# untitled.net
KiCad netlist of a schematic drawn in EAGLE
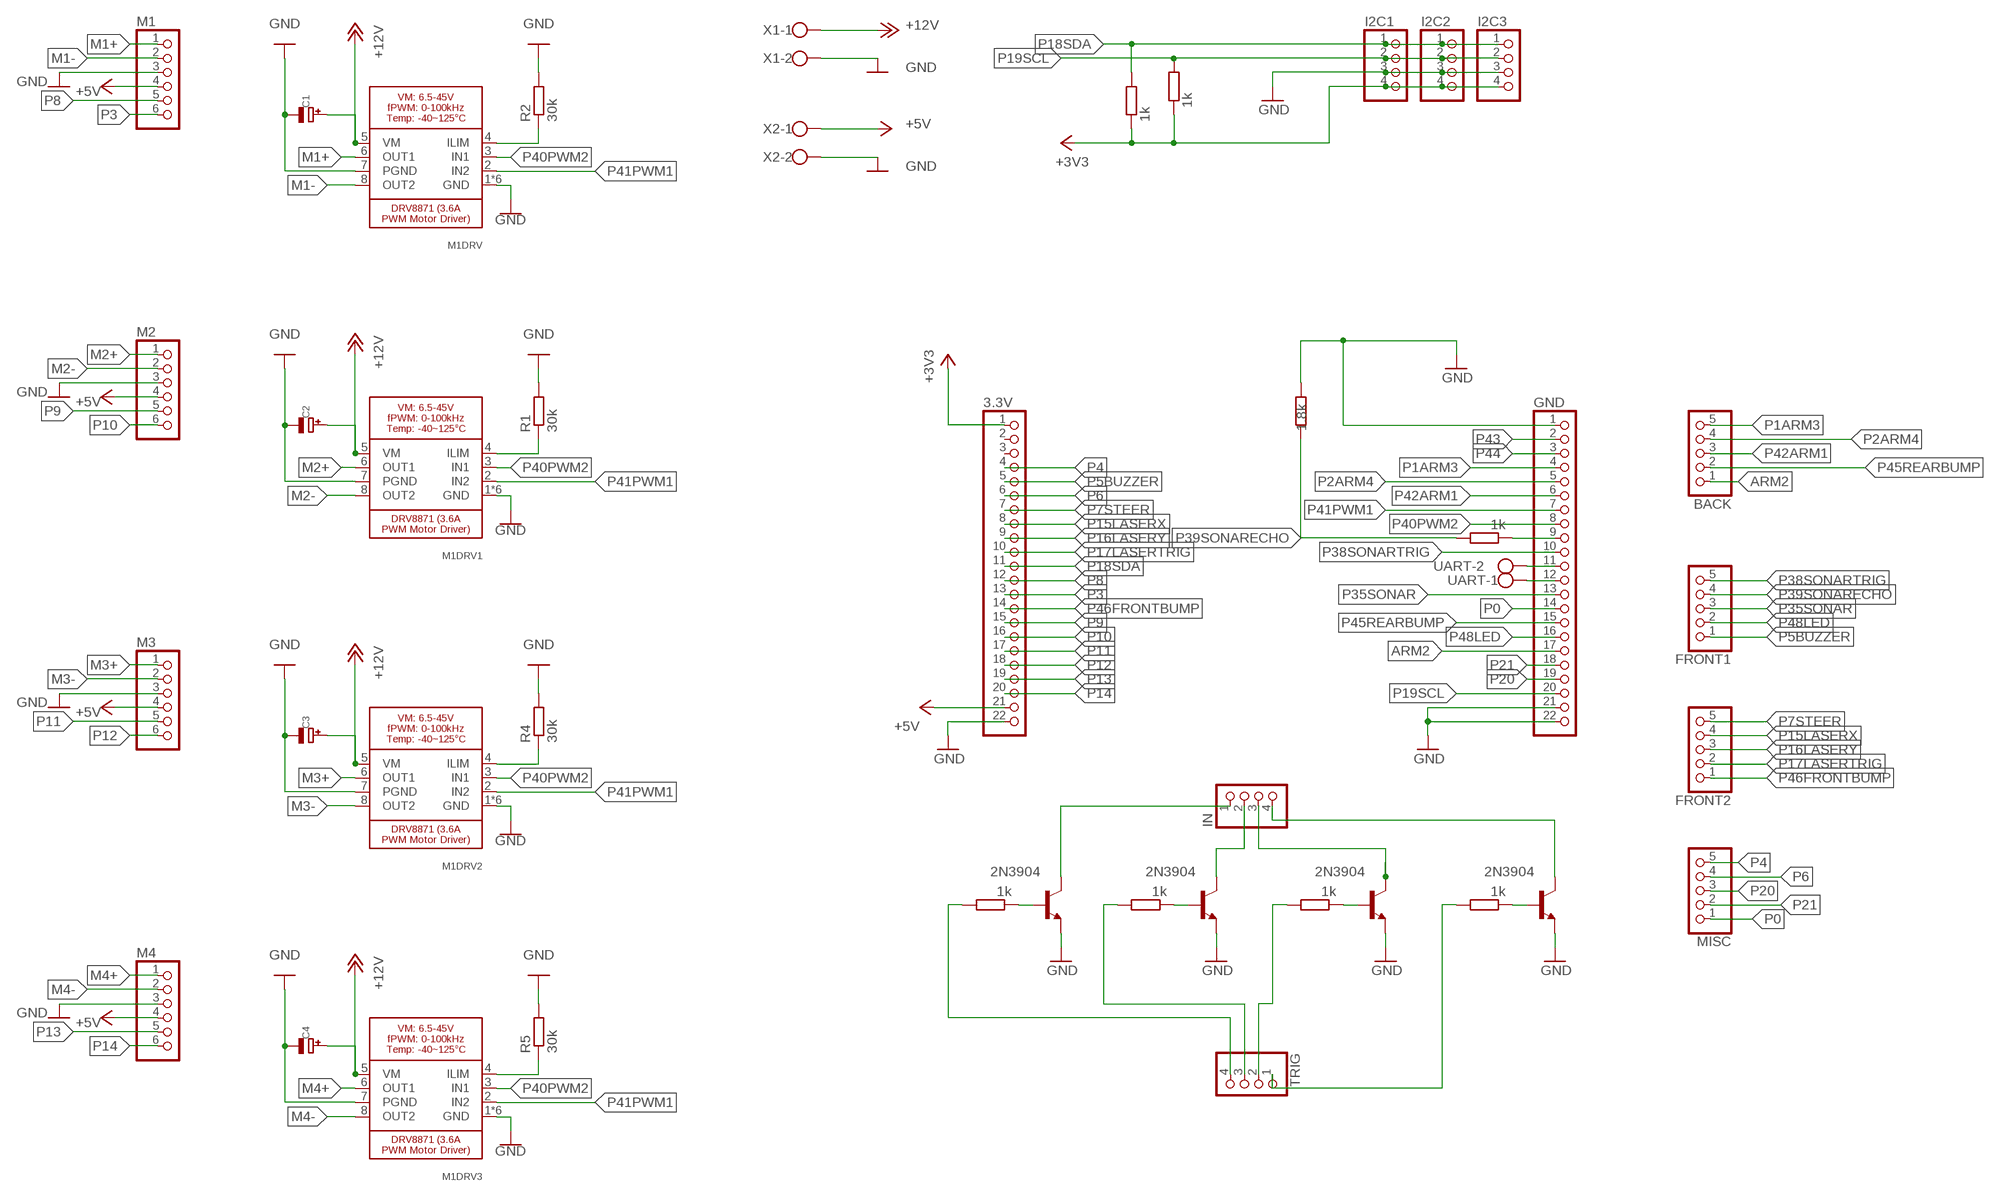
[diagram p0: schematic, sheet 1]

(export (version "E")
  (design (tool "Eeschema 10.0.6"))
  (components
    (comp (ref "1K")
      (value "1k")
      (footprint "eagle-import:0207_10")
      (libsource (lib "eagle-import") (part "R-EU_0207/10"))
    )
    (comp (ref "1K1")
      (value "1k")
      (footprint "eagle-import:0207_10")
      (libsource (lib "eagle-import") (part "R-EU_0207/10"))
    )
    (comp (ref "1K2")
      (value "1.8k")
      (footprint "eagle-import:0207_10")
      (libsource (lib "eagle-import") (part "R-EU_0207/10"))
    )
    (comp (ref "1K3")
      (value "1k")
      (footprint "eagle-import:0207_10")
      (libsource (lib "eagle-import") (part "R-EU_0207/10"))
    )
    (comp (ref "1K4")
      (value "1k")
      (footprint "eagle-import:0207_10")
      (libsource (lib "eagle-import") (part "R-EU_0207/10"))
    )
    (comp (ref "1K5")
      (value "1k")
      (footprint "eagle-import:0207_10")
      (libsource (lib "eagle-import") (part "R-EU_0207/10"))
    )
    (comp (ref "1K6")
      (value "1k")
      (footprint "eagle-import:0207_10")
      (libsource (lib "eagle-import") (part "R-EU_0207/10"))
    )
    (comp (ref "3.3V")
      (value "PINHD-1X22")
      (footprint "eagle-import:1X22")
      (libsource (lib "eagle-import") (part "PINHD-1X22"))
    )
    (comp (ref "BACK")
      (value "PINHD-1X5")
      (footprint "eagle-import:1X05")
      (libsource (lib "eagle-import") (part "PINHD-1X5"))
    )
    (comp (ref "C1")
      (value "MICROBUILDER_CAP_ELECTROLYTICPTH_3.5MMGRID_10MMDIA")
      (footprint "eagle-import:MICROBUILDER_CELEC_3.5MM_10MM")
      (libsource (lib "eagle-import") (part "MICROBUILDER_CAP_ELECTROLYTICPTH_3.5MMGRID_10MMDIA"))
    )
    (comp (ref "C2")
      (value "MICROBUILDER_CAP_ELECTROLYTICPTH_3.5MMGRID_10MMDIA")
      (footprint "eagle-import:MICROBUILDER_CELEC_3.5MM_10MM")
      (libsource (lib "eagle-import") (part "MICROBUILDER_CAP_ELECTROLYTICPTH_3.5MMGRID_10MMDIA"))
    )
    (comp (ref "C3")
      (value "MICROBUILDER_CAP_ELECTROLYTICPTH_3.5MMGRID_10MMDIA")
      (footprint "eagle-import:MICROBUILDER_CELEC_3.5MM_10MM")
      (libsource (lib "eagle-import") (part "MICROBUILDER_CAP_ELECTROLYTICPTH_3.5MMGRID_10MMDIA"))
    )
    (comp (ref "C4")
      (value "MICROBUILDER_CAP_ELECTROLYTICPTH_3.5MMGRID_10MMDIA")
      (footprint "eagle-import:MICROBUILDER_CELEC_3.5MM_10MM")
      (libsource (lib "eagle-import") (part "MICROBUILDER_CAP_ELECTROLYTICPTH_3.5MMGRID_10MMDIA"))
    )
    (comp (ref "FRONT1")
      (value "PINHD-1X5")
      (footprint "eagle-import:1X05")
      (libsource (lib "eagle-import") (part "PINHD-1X5"))
    )
    (comp (ref "FRONT2")
      (value "PINHD-1X5")
      (footprint "eagle-import:1X05")
      (libsource (lib "eagle-import") (part "PINHD-1X5"))
    )
    (comp (ref "GND")
      (value "PINHD-1X22")
      (footprint "eagle-import:1X22")
      (libsource (lib "eagle-import") (part "PINHD-1X22"))
    )
    (comp (ref "I2C1")
      (value "PINHD-1X4")
      (footprint "eagle-import:1X04")
      (libsource (lib "eagle-import") (part "PINHD-1X4"))
    )
    (comp (ref "I2C2")
      (value "PINHD-1X4")
      (footprint "eagle-import:1X04")
      (libsource (lib "eagle-import") (part "PINHD-1X4"))
    )
    (comp (ref "I2C3")
      (value "PINHD-1X4")
      (footprint "eagle-import:1X04")
      (libsource (lib "eagle-import") (part "PINHD-1X4"))
    )
    (comp (ref "IN")
      (value "PINHD-1X4")
      (footprint "eagle-import:1X04")
      (libsource (lib "eagle-import") (part "PINHD-1X4"))
    )
    (comp (ref "M1")
      (value "PINHD-1X6")
      (footprint "eagle-import:1X06")
      (libsource (lib "eagle-import") (part "PINHD-1X6"))
    )
    (comp (ref "M1DRV")
      (value "MICROBUILDER_DRV8871")
      (footprint "eagle-import:MICROBUILDER_HSOP8")
      (libsource (lib "eagle-import") (part "MICROBUILDER_DRV8871"))
    )
    (comp (ref "M1DRV1")
      (value "MICROBUILDER_DRV8871")
      (footprint "eagle-import:MICROBUILDER_HSOP8")
      (libsource (lib "eagle-import") (part "MICROBUILDER_DRV8871"))
    )
    (comp (ref "M1DRV2")
      (value "MICROBUILDER_DRV8871")
      (footprint "eagle-import:MICROBUILDER_HSOP8")
      (libsource (lib "eagle-import") (part "MICROBUILDER_DRV8871"))
    )
    (comp (ref "M1DRV3")
      (value "MICROBUILDER_DRV8871")
      (footprint "eagle-import:MICROBUILDER_HSOP8")
      (libsource (lib "eagle-import") (part "MICROBUILDER_DRV8871"))
    )
    (comp (ref "M2")
      (value "PINHD-1X6")
      (footprint "eagle-import:1X06")
      (libsource (lib "eagle-import") (part "PINHD-1X6"))
    )
    (comp (ref "M3")
      (value "PINHD-1X6")
      (footprint "eagle-import:1X06")
      (libsource (lib "eagle-import") (part "PINHD-1X6"))
    )
    (comp (ref "M4")
      (value "PINHD-1X6")
      (footprint "eagle-import:1X06")
      (libsource (lib "eagle-import") (part "PINHD-1X6"))
    )
    (comp (ref "MISC")
      (value "PINHD-1X5")
      (footprint "eagle-import:1X05")
      (libsource (lib "eagle-import") (part "PINHD-1X5"))
    )
    (comp (ref "R1")
      (value "30k")
      (footprint "eagle-import:0207_10")
      (libsource (lib "eagle-import") (part "R-EU_0207/10"))
    )
    (comp (ref "R2")
      (value "30k")
      (footprint "eagle-import:0207_10")
      (libsource (lib "eagle-import") (part "R-EU_0207/10"))
    )
    (comp (ref "R3")
      (value "1k")
      (footprint "eagle-import:0207_10")
      (libsource (lib "eagle-import") (part "R-EU_0207/10"))
    )
    (comp (ref "R4")
      (value "30k")
      (footprint "eagle-import:0207_10")
      (libsource (lib "eagle-import") (part "R-EU_0207/10"))
    )
    (comp (ref "R5")
      (value "30k")
      (footprint "eagle-import:0207_10")
      (libsource (lib "eagle-import") (part "R-EU_0207/10"))
    )
    (comp (ref "T1")
      (value "2N3904")
      (footprint "eagle-import:TO92")
      (libsource (lib "eagle-import") (part "2N3904"))
    )
    (comp (ref "T2")
      (value "2N3904")
      (footprint "eagle-import:TO92")
      (libsource (lib "eagle-import") (part "2N3904"))
    )
    (comp (ref "T3")
      (value "2N3904")
      (footprint "eagle-import:TO92")
      (libsource (lib "eagle-import") (part "2N3904"))
    )
    (comp (ref "T4")
      (value "2N3904")
      (footprint "eagle-import:TO92")
      (libsource (lib "eagle-import") (part "2N3904"))
    )
    (comp (ref "TRIG")
      (value "PINHD-1X4")
      (footprint "eagle-import:1X04")
      (libsource (lib "eagle-import") (part "PINHD-1X4"))
    )
    (comp (ref "UART")
      (value "W237-102")
      (footprint "eagle-import:W237-102")
      (fields (field (name "MPN") "237-102"))
      (libsource (lib "eagle-import") (part "W237-102"))
    )
    (comp (ref "X1")
      (value "W237-102")
      (footprint "eagle-import:W237-102")
      (fields (field (name "MPN") "237-102"))
      (libsource (lib "eagle-import") (part "W237-102"))
    )
    (comp (ref "X2")
      (value "W237-102")
      (footprint "eagle-import:W237-102")
      (fields (field (name "MPN") "237-102"))
      (libsource (lib "eagle-import") (part "W237-102"))
    )
  )
  (nets
    (net (code "1") (name "+3V3") (class "Default")
      (node (ref "1K") (pin "1") (pinfunction "1_1") (pintype "passive"))
      (node (ref "3.3V") (pin "1") (pinfunction "1_1") (pintype "passive"))
      (node (ref "I2C1") (pin "4") (pinfunction "4_4") (pintype "passive"))
      (node (ref "I2C2") (pin "4") (pinfunction "4_4") (pintype "passive"))
      (node (ref "I2C3") (pin "4") (pinfunction "4_4") (pintype "passive"))
      (node (ref "R3") (pin "1") (pinfunction "1_1") (pintype "passive"))
    )
    (net (code "2") (name "+5V") (class "Default")
      (node (ref "3.3V") (pin "21") (pinfunction "21_21") (pintype "passive"))
      (node (ref "M1") (pin "4") (pinfunction "4_4") (pintype "passive"))
      (node (ref "M2") (pin "4") (pinfunction "4_4") (pintype "passive"))
      (node (ref "M3") (pin "4") (pinfunction "4_4") (pintype "passive"))
      (node (ref "M4") (pin "4") (pinfunction "4_4") (pintype "passive"))
      (node (ref "X2") (pin "1") (pinfunction "KL_1") (pintype "passive"))
    )
    (net (code "3") (name "+12V") (class "Default")
      (node (ref "C1") (pin "+") (pinfunction "+_+") (pintype "passive"))
      (node (ref "C2") (pin "+") (pinfunction "+_+") (pintype "passive"))
      (node (ref "C3") (pin "+") (pinfunction "+_+") (pintype "passive"))
      (node (ref "C4") (pin "+") (pinfunction "+_+") (pintype "passive"))
      (node (ref "M1DRV") (pin "5") (pinfunction "VM_5") (pintype "power_in"))
      (node (ref "M1DRV1") (pin "5") (pinfunction "VM_5") (pintype "power_in"))
      (node (ref "M1DRV2") (pin "5") (pinfunction "VM_5") (pintype "power_in"))
      (node (ref "M1DRV3") (pin "5") (pinfunction "VM_5") (pintype "power_in"))
      (node (ref "X1") (pin "1") (pinfunction "KL_1") (pintype "passive"))
    )
    (net (code "4") (name "ARM2") (class "Default")
      (node (ref "BACK") (pin "1") (pinfunction "1_1") (pintype "passive"))
      (node (ref "GND") (pin "17") (pinfunction "17_17") (pintype "passive"))
    )
    (net (code "5") (name "GND") (class "Default")
      (node (ref "1K2") (pin "1") (pinfunction "1_1") (pintype "passive"))
      (node (ref "3.3V") (pin "22") (pinfunction "22_22") (pintype "passive"))
      (node (ref "C1") (pin "-") (pinfunction "-_-") (pintype "passive"))
      (node (ref "C2") (pin "-") (pinfunction "-_-") (pintype "passive"))
      (node (ref "C3") (pin "-") (pinfunction "-_-") (pintype "passive"))
      (node (ref "C4") (pin "-") (pinfunction "-_-") (pintype "passive"))
      (node (ref "GND") (pin "1") (pinfunction "1_1") (pintype "passive"))
      (node (ref "GND") (pin "21") (pinfunction "21_21") (pintype "passive"))
      (node (ref "GND") (pin "22") (pinfunction "22_22") (pintype "passive"))
      (node (ref "I2C1") (pin "3") (pinfunction "3_3") (pintype "passive"))
      (node (ref "I2C2") (pin "3") (pinfunction "3_3") (pintype "passive"))
      (node (ref "I2C3") (pin "3") (pinfunction "3_3") (pintype "passive"))
      (node (ref "M1") (pin "3") (pinfunction "3_3") (pintype "passive"))
      (node (ref "M1DRV") (pin "1") (pinfunction "GND_1") (pintype "power_in"))
      (node (ref "M1DRV") (pin "7") (pinfunction "PGND_7") (pintype "power_in"))
      (node (ref "M1DRV") (pin "GND") (pinfunction "GND_GND") (pintype "power_in"))
      (node (ref "M1DRV") (pin "P$1") (pinfunction "GND_P$1") (pintype "power_in"))
      (node (ref "M1DRV") (pin "P$2") (pinfunction "GND_P$2") (pintype "power_in"))
      (node (ref "M1DRV") (pin "P$3") (pinfunction "GND_P$3") (pintype "power_in"))
      (node (ref "M1DRV") (pin "P$4") (pinfunction "GND_P$4") (pintype "power_in"))
      (node (ref "M1DRV1") (pin "1") (pinfunction "GND_1") (pintype "power_in"))
      (node (ref "M1DRV1") (pin "7") (pinfunction "PGND_7") (pintype "power_in"))
      (node (ref "M1DRV1") (pin "GND") (pinfunction "GND_GND") (pintype "power_in"))
      (node (ref "M1DRV1") (pin "P$1") (pinfunction "GND_P$1") (pintype "power_in"))
      (node (ref "M1DRV1") (pin "P$2") (pinfunction "GND_P$2") (pintype "power_in"))
      (node (ref "M1DRV1") (pin "P$3") (pinfunction "GND_P$3") (pintype "power_in"))
      (node (ref "M1DRV1") (pin "P$4") (pinfunction "GND_P$4") (pintype "power_in"))
      (node (ref "M1DRV2") (pin "1") (pinfunction "GND_1") (pintype "power_in"))
      (node (ref "M1DRV2") (pin "7") (pinfunction "PGND_7") (pintype "power_in"))
      (node (ref "M1DRV2") (pin "GND") (pinfunction "GND_GND") (pintype "power_in"))
      (node (ref "M1DRV2") (pin "P$1") (pinfunction "GND_P$1") (pintype "power_in"))
      (node (ref "M1DRV2") (pin "P$2") (pinfunction "GND_P$2") (pintype "power_in"))
      (node (ref "M1DRV2") (pin "P$3") (pinfunction "GND_P$3") (pintype "power_in"))
      (node (ref "M1DRV2") (pin "P$4") (pinfunction "GND_P$4") (pintype "power_in"))
      (node (ref "M1DRV3") (pin "1") (pinfunction "GND_1") (pintype "power_in"))
      (node (ref "M1DRV3") (pin "7") (pinfunction "PGND_7") (pintype "power_in"))
      (node (ref "M1DRV3") (pin "GND") (pinfunction "GND_GND") (pintype "power_in"))
      (node (ref "M1DRV3") (pin "P$1") (pinfunction "GND_P$1") (pintype "power_in"))
      (node (ref "M1DRV3") (pin "P$2") (pinfunction "GND_P$2") (pintype "power_in"))
      (node (ref "M1DRV3") (pin "P$3") (pinfunction "GND_P$3") (pintype "power_in"))
      (node (ref "M1DRV3") (pin "P$4") (pinfunction "GND_P$4") (pintype "power_in"))
      (node (ref "M2") (pin "3") (pinfunction "3_3") (pintype "passive"))
      (node (ref "M3") (pin "3") (pinfunction "3_3") (pintype "passive"))
      (node (ref "M4") (pin "3") (pinfunction "3_3") (pintype "passive"))
      (node (ref "R1") (pin "2") (pinfunction "2_2") (pintype "passive"))
      (node (ref "R2") (pin "2") (pinfunction "2_2") (pintype "passive"))
      (node (ref "R4") (pin "2") (pinfunction "2_2") (pintype "passive"))
      (node (ref "R5") (pin "2") (pinfunction "2_2") (pintype "passive"))
      (node (ref "T1") (pin "3") (pinfunction "E_3") (pintype "passive"))
      (node (ref "T2") (pin "3") (pinfunction "E_3") (pintype "passive"))
      (node (ref "T3") (pin "3") (pinfunction "E_3") (pintype "passive"))
      (node (ref "T4") (pin "3") (pinfunction "E_3") (pintype "passive"))
      (node (ref "X1") (pin "2") (pinfunction "KL_2") (pintype "passive"))
      (node (ref "X2") (pin "2") (pinfunction "KL_2") (pintype "passive"))
    )
    (net (code "6") (name "M1+") (class "Default")
      (node (ref "M1") (pin "1") (pinfunction "1_1") (pintype "passive"))
      (node (ref "M1DRV") (pin "6") (pinfunction "OUT1_6") (pintype "output"))
    )
    (net (code "7") (name "M1-") (class "Default")
      (node (ref "M1") (pin "2") (pinfunction "2_2") (pintype "passive"))
      (node (ref "M1DRV") (pin "8") (pinfunction "OUT2_8") (pintype "output"))
    )
    (net (code "8") (name "M2+") (class "Default")
      (node (ref "M1DRV1") (pin "6") (pinfunction "OUT1_6") (pintype "output"))
      (node (ref "M2") (pin "1") (pinfunction "1_1") (pintype "passive"))
    )
    (net (code "9") (name "M2-") (class "Default")
      (node (ref "M1DRV1") (pin "8") (pinfunction "OUT2_8") (pintype "output"))
      (node (ref "M2") (pin "2") (pinfunction "2_2") (pintype "passive"))
    )
    (net (code "10") (name "M3+") (class "Default")
      (node (ref "M1DRV2") (pin "6") (pinfunction "OUT1_6") (pintype "output"))
      (node (ref "M3") (pin "1") (pinfunction "1_1") (pintype "passive"))
    )
    (net (code "11") (name "M3-") (class "Default")
      (node (ref "M1DRV2") (pin "8") (pinfunction "OUT2_8") (pintype "output"))
      (node (ref "M3") (pin "2") (pinfunction "2_2") (pintype "passive"))
    )
    (net (code "12") (name "M4+") (class "Default")
      (node (ref "M1DRV3") (pin "6") (pinfunction "OUT1_6") (pintype "output"))
      (node (ref "M4") (pin "1") (pinfunction "1_1") (pintype "passive"))
    )
    (net (code "13") (name "M4-") (class "Default")
      (node (ref "M1DRV3") (pin "8") (pinfunction "OUT2_8") (pintype "output"))
      (node (ref "M4") (pin "2") (pinfunction "2_2") (pintype "passive"))
    )
    (net (code "14") (name "Net-(1K1-Pad1)") (class "Default")
      (node (ref "1K1") (pin "1") (pinfunction "1_1") (pintype "passive"))
      (node (ref "GND") (pin "9") (pinfunction "9_9") (pintype "passive"))
    )
    (net (code "15") (name "Net-(1K3-Pad2)") (class "Default")
      (node (ref "1K3") (pin "2") (pinfunction "2_2") (pintype "passive"))
      (node (ref "TRIG") (pin "3") (pinfunction "3_3") (pintype "passive"))
    )
    (net (code "16") (name "Net-(1K4-Pad2)") (class "Default")
      (node (ref "1K4") (pin "2") (pinfunction "2_2") (pintype "passive"))
      (node (ref "TRIG") (pin "2") (pinfunction "2_2") (pintype "passive"))
    )
    (net (code "17") (name "Net-(1K5-Pad2)") (class "Default")
      (node (ref "1K5") (pin "2") (pinfunction "2_2") (pintype "passive"))
      (node (ref "TRIG") (pin "1") (pinfunction "1_1") (pintype "passive"))
    )
    (net (code "18") (name "Net-(1K6-Pad2)") (class "Default")
      (node (ref "1K6") (pin "2") (pinfunction "2_2") (pintype "passive"))
      (node (ref "TRIG") (pin "4") (pinfunction "4_4") (pintype "passive"))
    )
    (net (code "19") (name "Net-(M1DRV-ILIM)") (class "Default")
      (node (ref "M1DRV") (pin "4") (pinfunction "ILIM_4") (pintype "input"))
      (node (ref "R2") (pin "1") (pinfunction "1_1") (pintype "passive"))
    )
    (net (code "20") (name "Net-(M1DRV1-ILIM)") (class "Default")
      (node (ref "M1DRV1") (pin "4") (pinfunction "ILIM_4") (pintype "input"))
      (node (ref "R1") (pin "1") (pinfunction "1_1") (pintype "passive"))
    )
    (net (code "21") (name "Net-(M1DRV2-ILIM)") (class "Default")
      (node (ref "M1DRV2") (pin "4") (pinfunction "ILIM_4") (pintype "input"))
      (node (ref "R4") (pin "1") (pinfunction "1_1") (pintype "passive"))
    )
    (net (code "22") (name "Net-(M1DRV3-ILIM)") (class "Default")
      (node (ref "M1DRV3") (pin "4") (pinfunction "ILIM_4") (pintype "input"))
      (node (ref "R5") (pin "1") (pinfunction "1_1") (pintype "passive"))
    )
    (net (code "23") (name "Net-(T1-B)") (class "Default")
      (node (ref "1K3") (pin "1") (pinfunction "1_1") (pintype "passive"))
      (node (ref "T1") (pin "2") (pinfunction "B_2") (pintype "passive"))
    )
    (net (code "24") (name "Net-(T1-C)") (class "Default")
      (node (ref "IN") (pin "2") (pinfunction "2_2") (pintype "passive"))
      (node (ref "T1") (pin "1") (pinfunction "C_1") (pintype "passive"))
    )
    (net (code "25") (name "Net-(T2-B)") (class "Default")
      (node (ref "1K4") (pin "1") (pinfunction "1_1") (pintype "passive"))
      (node (ref "T2") (pin "2") (pinfunction "B_2") (pintype "passive"))
    )
    (net (code "26") (name "Net-(T2-C)") (class "Default")
      (node (ref "IN") (pin "3") (pinfunction "3_3") (pintype "passive"))
      (node (ref "T2") (pin "1") (pinfunction "C_1") (pintype "passive"))
    )
    (net (code "27") (name "Net-(T3-B)") (class "Default")
      (node (ref "1K5") (pin "1") (pinfunction "1_1") (pintype "passive"))
      (node (ref "T3") (pin "2") (pinfunction "B_2") (pintype "passive"))
    )
    (net (code "28") (name "Net-(T3-C)") (class "Default")
      (node (ref "IN") (pin "4") (pinfunction "4_4") (pintype "passive"))
      (node (ref "T3") (pin "1") (pinfunction "C_1") (pintype "passive"))
    )
    (net (code "29") (name "Net-(T4-B)") (class "Default")
      (node (ref "1K6") (pin "1") (pinfunction "1_1") (pintype "passive"))
      (node (ref "T4") (pin "2") (pinfunction "B_2") (pintype "passive"))
    )
    (net (code "30") (name "Net-(T4-C)") (class "Default")
      (node (ref "IN") (pin "1") (pinfunction "1_1") (pintype "passive"))
      (node (ref "T4") (pin "1") (pinfunction "C_1") (pintype "passive"))
    )
    (net (code "31") (name "Net-(UARTA-KL)") (class "Default")
      (node (ref "GND") (pin "12") (pinfunction "12_12") (pintype "passive"))
      (node (ref "UART") (pin "1") (pinfunction "KL_1") (pintype "passive"))
    )
    (net (code "32") (name "Net-(UARTB-KL)") (class "Default")
      (node (ref "GND") (pin "11") (pinfunction "11_11") (pintype "passive"))
      (node (ref "UART") (pin "2") (pinfunction "KL_2") (pintype "passive"))
    )
    (net (code "33") (name "P0") (class "Default")
      (node (ref "GND") (pin "14") (pinfunction "14_14") (pintype "passive"))
      (node (ref "MISC") (pin "1") (pinfunction "1_1") (pintype "passive"))
    )
    (net (code "34") (name "P1ARM3") (class "Default")
      (node (ref "BACK") (pin "5") (pinfunction "5_5") (pintype "passive"))
      (node (ref "GND") (pin "4") (pinfunction "4_4") (pintype "passive"))
    )
    (net (code "35") (name "P2ARM4") (class "Default")
      (node (ref "BACK") (pin "4") (pinfunction "4_4") (pintype "passive"))
      (node (ref "GND") (pin "5") (pinfunction "5_5") (pintype "passive"))
    )
    (net (code "36") (name "P3") (class "Default")
      (node (ref "3.3V") (pin "13") (pinfunction "13_13") (pintype "passive"))
      (node (ref "M1") (pin "6") (pinfunction "6_6") (pintype "passive"))
    )
    (net (code "37") (name "P4") (class "Default")
      (node (ref "3.3V") (pin "4") (pinfunction "4_4") (pintype "passive"))
      (node (ref "MISC") (pin "5") (pinfunction "5_5") (pintype "passive"))
    )
    (net (code "38") (name "P5BUZZER") (class "Default")
      (node (ref "3.3V") (pin "5") (pinfunction "5_5") (pintype "passive"))
      (node (ref "FRONT1") (pin "1") (pinfunction "1_1") (pintype "passive"))
    )
    (net (code "39") (name "P6") (class "Default")
      (node (ref "3.3V") (pin "6") (pinfunction "6_6") (pintype "passive"))
      (node (ref "MISC") (pin "4") (pinfunction "4_4") (pintype "passive"))
    )
    (net (code "40") (name "P7STEER") (class "Default")
      (node (ref "3.3V") (pin "7") (pinfunction "7_7") (pintype "passive"))
      (node (ref "FRONT2") (pin "5") (pinfunction "5_5") (pintype "passive"))
    )
    (net (code "41") (name "P8") (class "Default")
      (node (ref "3.3V") (pin "12") (pinfunction "12_12") (pintype "passive"))
      (node (ref "M1") (pin "5") (pinfunction "5_5") (pintype "passive"))
    )
    (net (code "42") (name "P9") (class "Default")
      (node (ref "3.3V") (pin "15") (pinfunction "15_15") (pintype "passive"))
      (node (ref "M2") (pin "5") (pinfunction "5_5") (pintype "passive"))
    )
    (net (code "43") (name "P10") (class "Default")
      (node (ref "3.3V") (pin "16") (pinfunction "16_16") (pintype "passive"))
      (node (ref "M2") (pin "6") (pinfunction "6_6") (pintype "passive"))
    )
    (net (code "44") (name "P11") (class "Default")
      (node (ref "3.3V") (pin "17") (pinfunction "17_17") (pintype "passive"))
      (node (ref "M3") (pin "5") (pinfunction "5_5") (pintype "passive"))
    )
    (net (code "45") (name "P12") (class "Default")
      (node (ref "3.3V") (pin "18") (pinfunction "18_18") (pintype "passive"))
      (node (ref "M3") (pin "6") (pinfunction "6_6") (pintype "passive"))
    )
    (net (code "46") (name "P13") (class "Default")
      (node (ref "3.3V") (pin "19") (pinfunction "19_19") (pintype "passive"))
      (node (ref "M4") (pin "5") (pinfunction "5_5") (pintype "passive"))
    )
    (net (code "47") (name "P14") (class "Default")
      (node (ref "3.3V") (pin "20") (pinfunction "20_20") (pintype "passive"))
      (node (ref "M4") (pin "6") (pinfunction "6_6") (pintype "passive"))
    )
    (net (code "48") (name "P15LASERX") (class "Default")
      (node (ref "3.3V") (pin "8") (pinfunction "8_8") (pintype "passive"))
      (node (ref "FRONT2") (pin "4") (pinfunction "4_4") (pintype "passive"))
    )
    (net (code "49") (name "P16LASERY") (class "Default")
      (node (ref "3.3V") (pin "9") (pinfunction "9_9") (pintype "passive"))
      (node (ref "FRONT2") (pin "3") (pinfunction "3_3") (pintype "passive"))
    )
    (net (code "50") (name "P17LASERTRIG") (class "Default")
      (node (ref "3.3V") (pin "10") (pinfunction "10_10") (pintype "passive"))
      (node (ref "FRONT2") (pin "2") (pinfunction "2_2") (pintype "passive"))
    )
    (net (code "51") (name "P18SDA") (class "Default")
      (node (ref "1K") (pin "2") (pinfunction "2_2") (pintype "passive"))
      (node (ref "3.3V") (pin "11") (pinfunction "11_11") (pintype "passive"))
      (node (ref "I2C1") (pin "1") (pinfunction "1_1") (pintype "passive"))
      (node (ref "I2C2") (pin "1") (pinfunction "1_1") (pintype "passive"))
      (node (ref "I2C3") (pin "1") (pinfunction "1_1") (pintype "passive"))
    )
    (net (code "52") (name "P19SCL") (class "Default")
      (node (ref "GND") (pin "20") (pinfunction "20_20") (pintype "passive"))
      (node (ref "I2C1") (pin "2") (pinfunction "2_2") (pintype "passive"))
      (node (ref "I2C2") (pin "2") (pinfunction "2_2") (pintype "passive"))
      (node (ref "I2C3") (pin "2") (pinfunction "2_2") (pintype "passive"))
      (node (ref "R3") (pin "2") (pinfunction "2_2") (pintype "passive"))
    )
    (net (code "53") (name "P20") (class "Default")
      (node (ref "GND") (pin "19") (pinfunction "19_19") (pintype "passive"))
      (node (ref "MISC") (pin "3") (pinfunction "3_3") (pintype "passive"))
    )
    (net (code "54") (name "P21") (class "Default")
      (node (ref "GND") (pin "18") (pinfunction "18_18") (pintype "passive"))
      (node (ref "MISC") (pin "2") (pinfunction "2_2") (pintype "passive"))
    )
    (net (code "55") (name "P35SONAR") (class "Default")
      (node (ref "FRONT1") (pin "3") (pinfunction "3_3") (pintype "passive"))
      (node (ref "GND") (pin "13") (pinfunction "13_13") (pintype "passive"))
    )
    (net (code "56") (name "P38SONARTRIG") (class "Default")
      (node (ref "FRONT1") (pin "5") (pinfunction "5_5") (pintype "passive"))
      (node (ref "GND") (pin "10") (pinfunction "10_10") (pintype "passive"))
    )
    (net (code "57") (name "P39SONARECHO") (class "Default")
      (node (ref "1K1") (pin "2") (pinfunction "2_2") (pintype "passive"))
      (node (ref "1K2") (pin "2") (pinfunction "2_2") (pintype "passive"))
      (node (ref "FRONT1") (pin "4") (pinfunction "4_4") (pintype "passive"))
    )
    (net (code "58") (name "P40PWM2") (class "Default")
      (node (ref "GND") (pin "8") (pinfunction "8_8") (pintype "passive"))
      (node (ref "M1DRV") (pin "3") (pinfunction "IN1_3") (pintype "input"))
      (node (ref "M1DRV1") (pin "3") (pinfunction "IN1_3") (pintype "input"))
      (node (ref "M1DRV2") (pin "3") (pinfunction "IN1_3") (pintype "input"))
      (node (ref "M1DRV3") (pin "3") (pinfunction "IN1_3") (pintype "input"))
    )
    (net (code "59") (name "P41PWM1") (class "Default")
      (node (ref "GND") (pin "7") (pinfunction "7_7") (pintype "passive"))
      (node (ref "M1DRV") (pin "2") (pinfunction "IN2_2") (pintype "input"))
      (node (ref "M1DRV1") (pin "2") (pinfunction "IN2_2") (pintype "input"))
      (node (ref "M1DRV2") (pin "2") (pinfunction "IN2_2") (pintype "input"))
      (node (ref "M1DRV3") (pin "2") (pinfunction "IN2_2") (pintype "input"))
    )
    (net (code "60") (name "P42ARM1") (class "Default")
      (node (ref "BACK") (pin "3") (pinfunction "3_3") (pintype "passive"))
      (node (ref "GND") (pin "6") (pinfunction "6_6") (pintype "passive"))
    )
    (net (code "61") (name "P43") (class "Default")
      (node (ref "GND") (pin "2") (pinfunction "2_2") (pintype "passive"))
    )
    (net (code "62") (name "P44") (class "Default")
      (node (ref "GND") (pin "3") (pinfunction "3_3") (pintype "passive"))
    )
    (net (code "63") (name "P45REARBUMP") (class "Default")
      (node (ref "BACK") (pin "2") (pinfunction "2_2") (pintype "passive"))
      (node (ref "GND") (pin "15") (pinfunction "15_15") (pintype "passive"))
    )
    (net (code "64") (name "P46FRONTBUMP") (class "Default")
      (node (ref "3.3V") (pin "14") (pinfunction "14_14") (pintype "passive"))
      (node (ref "FRONT2") (pin "1") (pinfunction "1_1") (pintype "passive"))
    )
    (net (code "65") (name "P48LED") (class "Default")
      (node (ref "FRONT1") (pin "2") (pinfunction "2_2") (pintype "passive"))
      (node (ref "GND") (pin "16") (pinfunction "16_16") (pintype "passive"))
    )
    (net (code "66") (name "unconnected-(3.3V-Pad2)") (class "Default")
      (node (ref "3.3V") (pin "2") (pinfunction "2_2") (pintype "passive"))
    )
    (net (code "67") (name "unconnected-(3.3V-Pad3)") (class "Default")
      (node (ref "3.3V") (pin "3") (pinfunction "3_3") (pintype "passive"))
    )
  )
)
